# flex_sensors_two_types.net
KiCad netlist of a schematic drawn in EAGLE
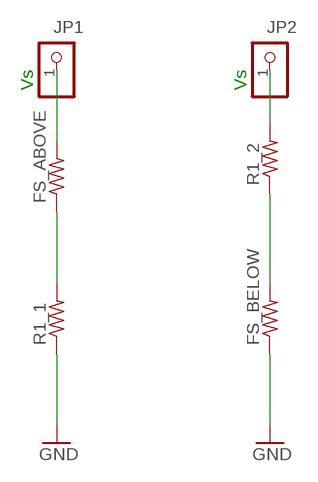
[diagram p0: schematic, sheet 1]

(export (version "E")
  (design (tool "Eeschema 10.0.6"))
  (components
    (comp (ref "FS_ABOVE")
      (value "R-US_0207/5V")
      (footprint "eagle-import:0207_5V")
      (libsource (lib "eagle-import") (part "R-US_0207/5V"))
    )
    (comp (ref "FS_BELOW")
      (value "R-US_0207/5V")
      (footprint "eagle-import:0207_5V")
      (libsource (lib "eagle-import") (part "R-US_0207/5V"))
    )
    (comp (ref "JP1")
      (value "PINHD-1X1")
      (footprint "eagle-import:1X01")
      (libsource (lib "eagle-import") (part "PINHD-1X1"))
    )
    (comp (ref "JP2")
      (value "PINHD-1X1")
      (footprint "eagle-import:1X01")
      (libsource (lib "eagle-import") (part "PINHD-1X1"))
    )
    (comp (ref "R1_1")
      (value "R-US_0207/5V")
      (footprint "eagle-import:0207_5V")
      (libsource (lib "eagle-import") (part "R-US_0207/5V"))
    )
    (comp (ref "R1_2")
      (value "R-US_0207/5V")
      (footprint "eagle-import:0207_5V")
      (libsource (lib "eagle-import") (part "R-US_0207/5V"))
    )
  )
  (nets
    (net (code "1") (name "GND") (class "Default")
      (node (ref "FS_BELOW") (pin "1") (pinfunction "1_1") (pintype "passive"))
      (node (ref "R1_1") (pin "1") (pinfunction "1_1") (pintype "passive"))
    )
    (net (code "2") (name "Net-(FS_ABOVE-Pad1)") (class "Default")
      (node (ref "FS_ABOVE") (pin "1") (pinfunction "1_1") (pintype "passive"))
      (node (ref "R1_1") (pin "2") (pinfunction "2_2") (pintype "passive"))
    )
    (net (code "3") (name "Net-(FS_ABOVE-Pad2)") (class "Default")
      (node (ref "FS_ABOVE") (pin "2") (pinfunction "2_2") (pintype "passive"))
      (node (ref "JP1") (pin "1") (pinfunction "1_1") (pintype "passive"))
    )
    (net (code "4") (name "Net-(FS_BELOW-Pad2)") (class "Default")
      (node (ref "FS_BELOW") (pin "2") (pinfunction "2_2") (pintype "passive"))
      (node (ref "R1_2") (pin "1") (pinfunction "1_1") (pintype "passive"))
    )
    (net (code "5") (name "Net-(JP2-Pad1)") (class "Default")
      (node (ref "JP2") (pin "1") (pinfunction "1_1") (pintype "passive"))
      (node (ref "R1_2") (pin "2") (pinfunction "2_2") (pintype "passive"))
    )
  )
)
